# misc.net
KiCad netlist of a schematic drawn in Altium Designer
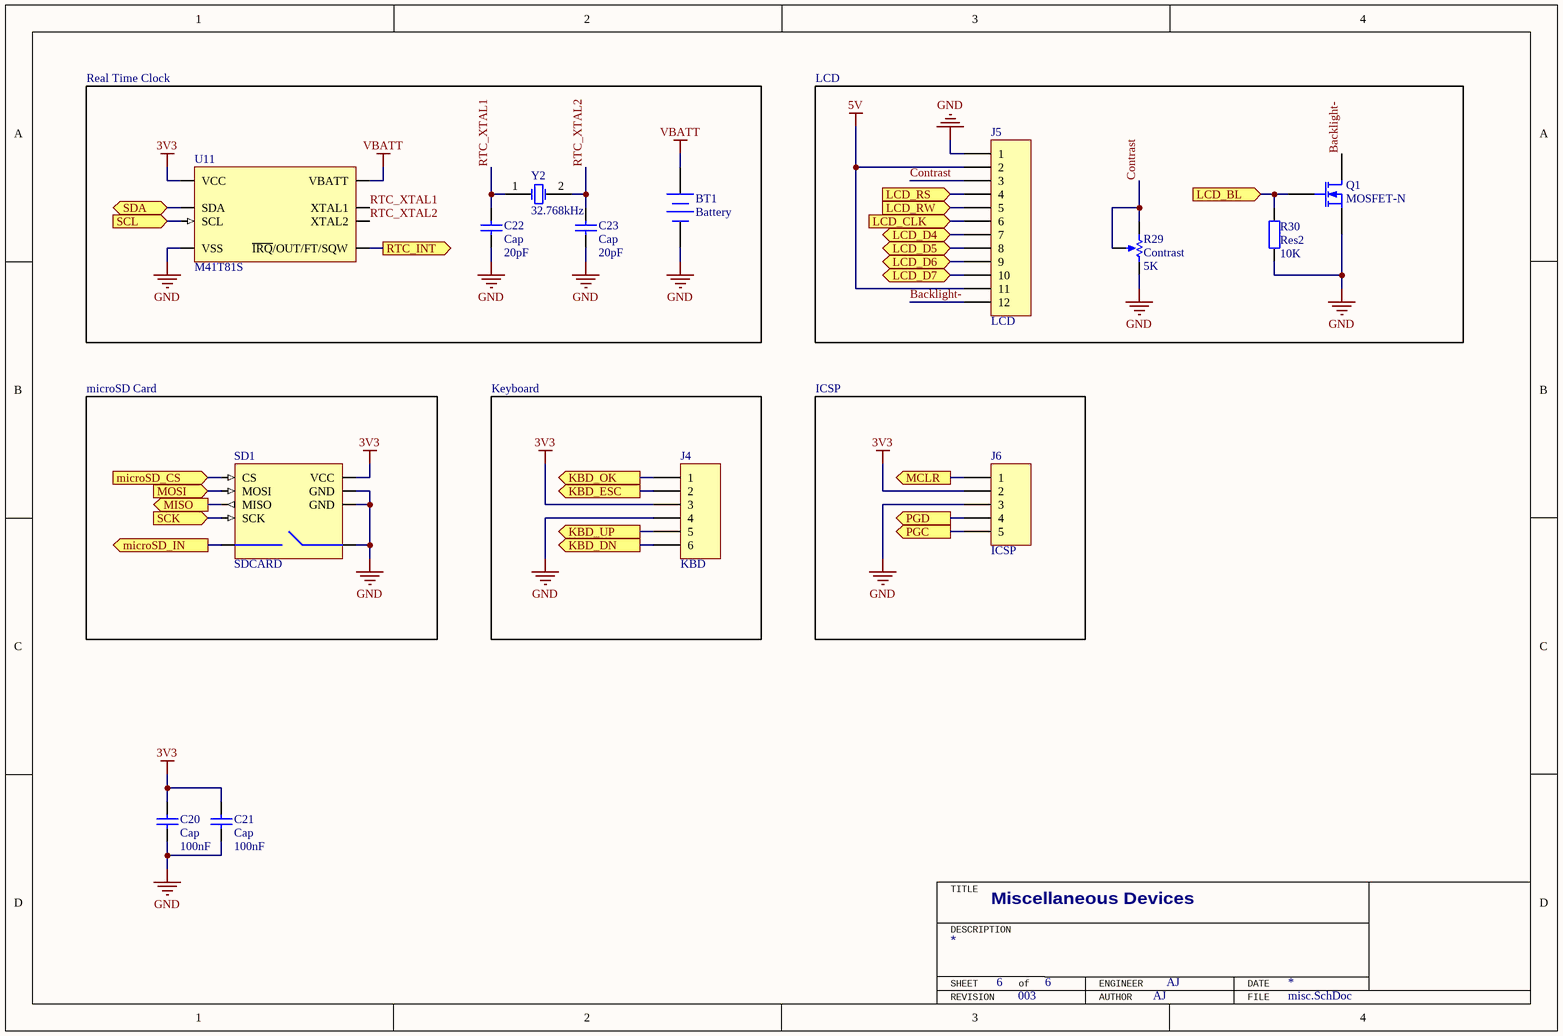
[diagram p0: misc.SchDoc]

(export (version "E")
  (design (tool "Eeschema 10.0.6"))
  (components
    (comp (ref "BT1")
      (value "Battery")
      (footprint "Coin Cell")
      (description "Multicell Battery")
      (fields (field (name "PUBLISHER") "Altium Limited"))
      (libsource (lib "Miscellaneous Devices") (part "Battery"))
    )
    (comp (ref "C20")
      (value "Cap")
      (footprint "0603")
      (description "Capacitor")
      (fields (field (name "ALTIUM_VALUE") "100nF") (field (name "PUBLISHER") "Altium Limited"))
      (libsource (lib "Miscellaneous Devices") (part "Cap"))
    )
    (comp (ref "C21")
      (value "Cap")
      (footprint "0603")
      (description "Capacitor")
      (fields (field (name "ALTIUM_VALUE") "100nF") (field (name "PUBLISHER") "Altium Limited"))
      (libsource (lib "Miscellaneous Devices") (part "Cap"))
    )
    (comp (ref "C22")
      (value "Cap")
      (footprint "0603")
      (description "Capacitor")
      (fields (field (name "ALTIUM_VALUE") "20pF") (field (name "PUBLISHER") "Altium Limited"))
      (libsource (lib "Miscellaneous Devices") (part "Cap"))
    )
    (comp (ref "C23")
      (value "Cap")
      (footprint "0603")
      (description "Capacitor")
      (fields (field (name "ALTIUM_VALUE") "20pF") (field (name "PUBLISHER") "Altium Limited"))
      (libsource (lib "Miscellaneous Devices") (part "Cap"))
    )
    (comp (ref "J4")
      (value "KBD")
      (footprint "HDR1X6")
      (description "Header, 6-Pin")
      (fields (field (name "PUBLISHER") "Altium Limited"))
      (libsource (lib "Miscellaneous Connectors") (part "Header 6"))
    )
    (comp (ref "J5")
      (value "LCD")
      (footprint "HDR1X12")
      (description "Header, 12-Pin")
      (fields (field (name "PUBLISHER") "Altium Limited"))
      (libsource (lib "Miscellaneous Connectors") (part "Header 12"))
    )
    (comp (ref "J6")
      (value "ICSP")
      (footprint "HDR1X5")
      (description "Header, 5-Pin")
      (fields (field (name "PUBLISHER") "Altium Limited"))
      (libsource (lib "Miscellaneous Connectors") (part "Header 5"))
    )
    (comp (ref "Q1")
      (value "MOSFET-N")
      (footprint "SOT323")
      (description "N-Channel MOSFET")
      (fields (field (name "PUBLISHER") "Altium Limited"))
      (libsource (lib "Miscellaneous Devices") (part "MOSFET-N"))
    )
    (comp (ref "R29")
      (value "Contrast")
      (footprint "Potentiometer")
      (description "Potentiometer")
      (fields (field (name "ALTIUM_VALUE") "5K") (field (name "PUBLISHER") "Altium Limited"))
      (libsource (lib "Miscellaneous Devices") (part "RPot"))
    )
    (comp (ref "R30")
      (value "Res2")
      (footprint "0603")
      (description "Resistor")
      (fields (field (name "ALTIUM_VALUE") "10K") (field (name "PUBLISHER") "Altium Limited"))
      (libsource (lib "Miscellaneous Devices") (part "Res2"))
    )
    (comp (ref "SD1")
      (value "SDCARD")
      (footprint "microSD connector")
      (description "SD Card, SPI interface")
      (libsource (lib "AJ") (part "SD Card"))
    )
    (comp (ref "U11")
      (value "M41T81S")
      (footprint "SO-8")
      (description "Serial access real-time clock with alarms")
      (libsource (lib "AJ") (part "M41T81S"))
    )
    (comp (ref "Y2")
      (value "32.768kHz")
      (footprint "CM200S")
      (description "Crystal Oscillator")
      (fields (field (name "PUBLISHER") "Altium Limited"))
      (libsource (lib "Miscellaneous Devices") (part "XTAL"))
    )
  )
  (nets
    (net (code "1") (name "/Backlight-") (class "Default")
      (node (ref "J5") (pin "12") (pinfunction "12_12") (pintype "passive"))
      (node (ref "Q1") (pin "1") (pinfunction "D_1") (pintype "passive"))
    )
    (net (code "2") (name "/Contrast") (class "Default")
      (node (ref "J5") (pin "3") (pinfunction "3_3") (pintype "passive"))
      (node (ref "R29") (pin "1") (pinfunction "TOP_1") (pintype "passive"))
      (node (ref "R29") (pin "3") (pinfunction "TAP_3") (pintype "passive"))
    )
    (net (code "3") (name "/KBD_DN") (class "Default")
      (node (ref "J4") (pin "6") (pinfunction "6_6") (pintype "passive"))
    )
    (net (code "4") (name "/KBD_ESC") (class "Default")
      (node (ref "J4") (pin "2") (pinfunction "2_2") (pintype "passive"))
    )
    (net (code "5") (name "/KBD_OK") (class "Default")
      (node (ref "J4") (pin "1") (pinfunction "1_1") (pintype "passive"))
    )
    (net (code "6") (name "/KBD_UP") (class "Default")
      (node (ref "J4") (pin "5") (pinfunction "5_5") (pintype "passive"))
    )
    (net (code "7") (name "/LCD_BL") (class "Default")
      (node (ref "Q1") (pin "2") (pinfunction "G_2") (pintype "passive"))
      (node (ref "R30") (pin "2") (pinfunction "2_2") (pintype "passive"))
    )
    (net (code "8") (name "/LCD_CLK") (class "Default")
      (node (ref "J5") (pin "6") (pinfunction "6_6") (pintype "passive"))
    )
    (net (code "9") (name "/LCD_D4") (class "Default")
      (node (ref "J5") (pin "7") (pinfunction "7_7") (pintype "passive"))
    )
    (net (code "10") (name "/LCD_D5") (class "Default")
      (node (ref "J5") (pin "8") (pinfunction "8_8") (pintype "passive"))
    )
    (net (code "11") (name "/LCD_D6") (class "Default")
      (node (ref "J5") (pin "9") (pinfunction "9_9") (pintype "passive"))
    )
    (net (code "12") (name "/LCD_D7") (class "Default")
      (node (ref "J5") (pin "10") (pinfunction "10_10") (pintype "passive"))
    )
    (net (code "13") (name "/LCD_RS") (class "Default")
      (node (ref "J5") (pin "4") (pinfunction "4_4") (pintype "passive"))
    )
    (net (code "14") (name "/LCD_RW") (class "Default")
      (node (ref "J5") (pin "5") (pinfunction "5_5") (pintype "passive"))
    )
    (net (code "15") (name "/MCLR") (class "Default")
      (node (ref "J6") (pin "1") (pinfunction "1_1") (pintype "passive"))
    )
    (net (code "16") (name "/MISO") (class "Default")
      (node (ref "SD1") (pin "7") (pinfunction "MISO_7") (pintype "output"))
    )
    (net (code "17") (name "/MOSI") (class "Default")
      (node (ref "SD1") (pin "2") (pinfunction "MOSI_2") (pintype "input"))
    )
    (net (code "18") (name "/PGC") (class "Default")
      (node (ref "J6") (pin "5") (pinfunction "5_5") (pintype "passive"))
    )
    (net (code "19") (name "/PGD") (class "Default")
      (node (ref "J6") (pin "4") (pinfunction "4_4") (pintype "passive"))
    )
    (net (code "20") (name "/RTC_INT") (class "Default")
      (node (ref "U11") (pin "7") (pinfunction "~{IRQ}/OUT/FT/SQW_7") (pintype "passive"))
    )
    (net (code "21") (name "/RTC_XTAL1") (class "Default")
      (node (ref "C22") (pin "2") (pinfunction "2_2") (pintype "passive"))
      (node (ref "U11") (pin "1") (pinfunction "XTAL1_1") (pintype "passive"))
      (node (ref "Y2") (pin "1") (pinfunction "OSC1_1") (pintype "passive"))
    )
    (net (code "22") (name "/RTC_XTAL2") (class "Default")
      (node (ref "C23") (pin "2") (pinfunction "2_2") (pintype "passive"))
      (node (ref "U11") (pin "2") (pinfunction "XTAL2_2") (pintype "passive"))
      (node (ref "Y2") (pin "2") (pinfunction "OSC2_2") (pintype "passive"))
    )
    (net (code "23") (name "/SCK") (class "Default")
      (node (ref "SD1") (pin "5") (pinfunction "SCK_5") (pintype "input"))
    )
    (net (code "24") (name "/SCL") (class "Default")
      (node (ref "U11") (pin "6") (pinfunction "SCL_6") (pintype "input"))
    )
    (net (code "25") (name "/SDA") (class "Default")
      (node (ref "U11") (pin "5") (pinfunction "SDA_5") (pintype "bidirectional"))
    )
    (net (code "26") (name "/microSD_CS") (class "Default")
      (node (ref "SD1") (pin "1") (pinfunction "CS_1") (pintype "input"))
    )
    (net (code "27") (name "/microSD_IN") (class "Default")
      (node (ref "SD1") (pin "9") (pinfunction "A_9") (pintype "passive"))
    )
    (net (code "28") (name "3V3") (class "Default")
      (node (ref "C20") (pin "2") (pinfunction "2_2") (pintype "passive"))
      (node (ref "C21") (pin "2") (pinfunction "2_2") (pintype "passive"))
      (node (ref "J4") (pin "3") (pinfunction "3_3") (pintype "passive"))
      (node (ref "J6") (pin "2") (pinfunction "2_2") (pintype "passive"))
      (node (ref "SD1") (pin "4") (pinfunction "VCC_4") (pintype "power_in"))
      (node (ref "U11") (pin "8") (pinfunction "VCC_8") (pintype "power_in"))
    )
    (net (code "29") (name "5V") (class "Default")
      (node (ref "J5") (pin "11") (pinfunction "11_11") (pintype "passive"))
      (node (ref "J5") (pin "2") (pinfunction "2_2") (pintype "passive"))
    )
    (net (code "30") (name "GND") (class "Default")
      (node (ref "BT1") (pin "2") (pinfunction "-_2") (pintype "passive"))
      (node (ref "C20") (pin "1") (pinfunction "1_1") (pintype "passive"))
      (node (ref "C21") (pin "1") (pinfunction "1_1") (pintype "passive"))
      (node (ref "C22") (pin "1") (pinfunction "1_1") (pintype "passive"))
      (node (ref "C23") (pin "1") (pinfunction "1_1") (pintype "passive"))
      (node (ref "J4") (pin "4") (pinfunction "4_4") (pintype "passive"))
      (node (ref "J5") (pin "1") (pinfunction "1_1") (pintype "passive"))
      (node (ref "J6") (pin "3") (pinfunction "3_3") (pintype "passive"))
      (node (ref "Q1") (pin "3") (pinfunction "S_3") (pintype "passive"))
      (node (ref "R29") (pin "2") (pinfunction "BOT_2") (pintype "passive"))
      (node (ref "R30") (pin "1") (pinfunction "1_1") (pintype "passive"))
      (node (ref "SD1") (pin "10") (pinfunction "B_10") (pintype "passive"))
      (node (ref "SD1") (pin "3") (pinfunction "GND_3") (pintype "power_in"))
      (node (ref "SD1") (pin "6") (pinfunction "GND_6") (pintype "power_in"))
      (node (ref "U11") (pin "4") (pinfunction "VSS_4") (pintype "power_in"))
    )
    (net (code "31") (name "VBATT") (class "Default")
      (node (ref "BT1") (pin "1") (pinfunction "+_1") (pintype "passive"))
      (node (ref "U11") (pin "3") (pinfunction "VBATT_3") (pintype "power_in"))
    )
  )
)
